# HInata-debug-board.net
KiCad netlist of a schematic drawn in EAGLE
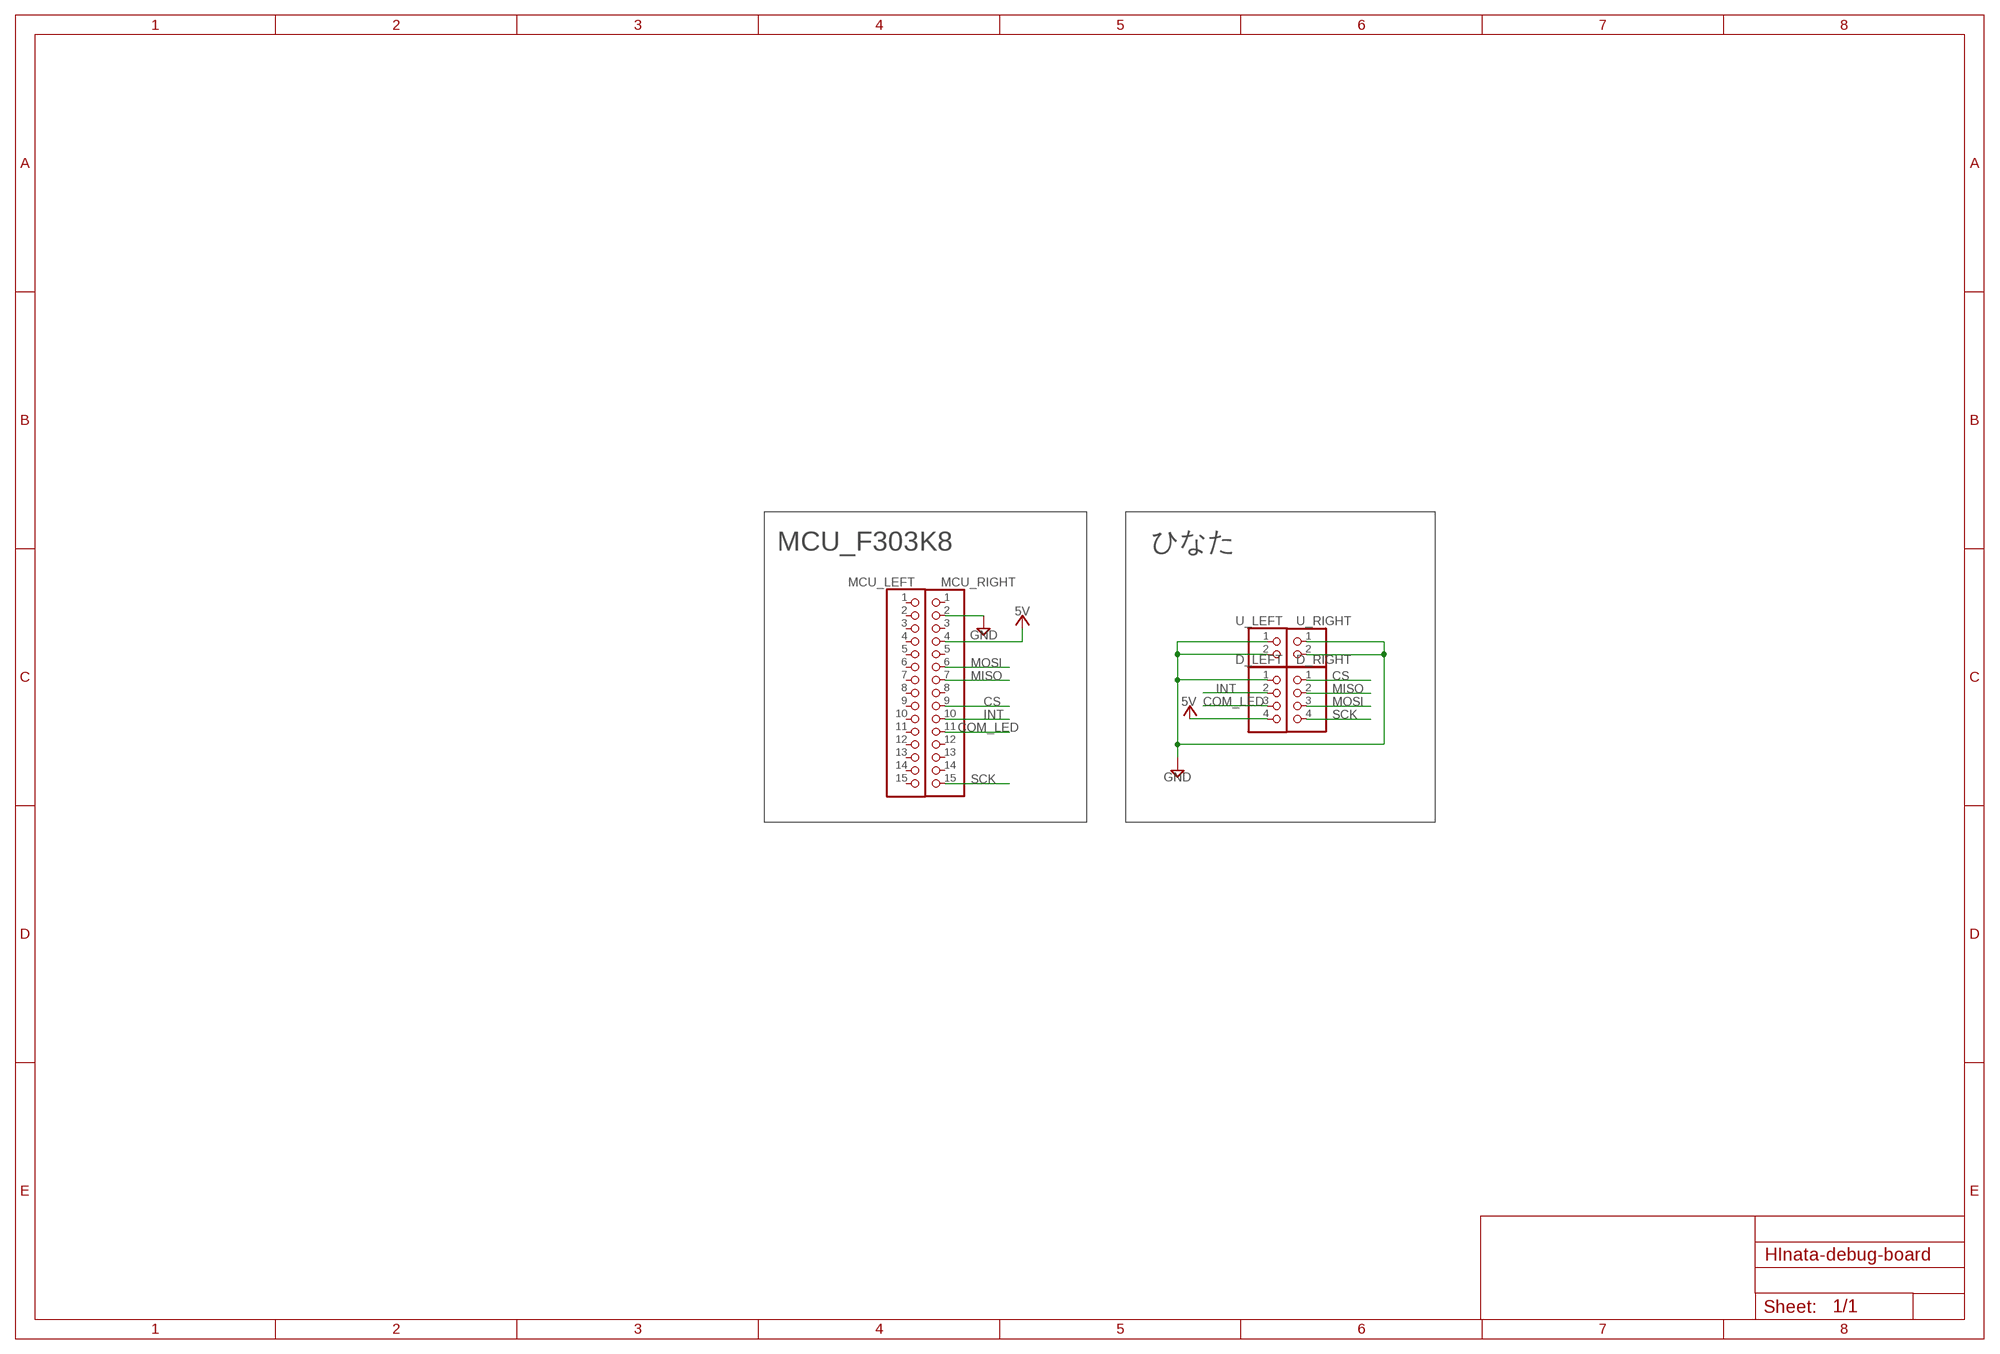
[diagram p0: schematic, sheet 1]

(export (version "E")
  (design (tool "Eeschema 10.0.6"))
  (components
    (comp (ref "D_LEFT")
      (value "PINHD-1X4")
      (footprint "eagle-import:1X04")
      (libsource (lib "eagle-import") (part "PINHD-1X4"))
    )
    (comp (ref "D_RIGHT")
      (value "PINHD-1X4")
      (footprint "eagle-import:1X04")
      (libsource (lib "eagle-import") (part "PINHD-1X4"))
    )
    (comp (ref "MCU_LEFT")
      (value "PINHD-1X15")
      (footprint "eagle-import:1X15")
      (libsource (lib "eagle-import") (part "PINHD-1X15"))
    )
    (comp (ref "MCU_RIGHT")
      (value "PINHD-1X15")
      (footprint "eagle-import:1X15")
      (libsource (lib "eagle-import") (part "PINHD-1X15"))
    )
    (comp (ref "U_LEFT")
      (value "PINHD-1X2")
      (footprint "eagle-import:1X02")
      (libsource (lib "eagle-import") (part "PINHD-1X2"))
    )
    (comp (ref "U_RIGHT")
      (value "PINHD-1X2")
      (footprint "eagle-import:1X02")
      (libsource (lib "eagle-import") (part "PINHD-1X2"))
    )
  )
  (nets
    (net (code "1") (name "/COM_LED") (class "Default")
      (node (ref "D_LEFT") (pin "3") (pinfunction "3_3") (pintype "passive"))
      (node (ref "MCU_RIGHT") (pin "11") (pinfunction "11_11") (pintype "passive"))
    )
    (net (code "2") (name "/CS") (class "Default")
      (node (ref "D_RIGHT") (pin "1") (pinfunction "1_1") (pintype "passive"))
      (node (ref "MCU_RIGHT") (pin "9") (pinfunction "9_9") (pintype "passive"))
    )
    (net (code "3") (name "/INT") (class "Default")
      (node (ref "D_LEFT") (pin "2") (pinfunction "2_2") (pintype "passive"))
      (node (ref "MCU_RIGHT") (pin "10") (pinfunction "10_10") (pintype "passive"))
    )
    (net (code "4") (name "/MISO") (class "Default")
      (node (ref "D_RIGHT") (pin "2") (pinfunction "2_2") (pintype "passive"))
      (node (ref "MCU_RIGHT") (pin "7") (pinfunction "7_7") (pintype "passive"))
    )
    (net (code "5") (name "/MOSI") (class "Default")
      (node (ref "D_RIGHT") (pin "3") (pinfunction "3_3") (pintype "passive"))
      (node (ref "MCU_RIGHT") (pin "6") (pinfunction "6_6") (pintype "passive"))
    )
    (net (code "6") (name "/SCK") (class "Default")
      (node (ref "D_RIGHT") (pin "4") (pinfunction "4_4") (pintype "passive"))
      (node (ref "MCU_RIGHT") (pin "15") (pinfunction "15_15") (pintype "passive"))
    )
    (net (code "7") (name "GND") (class "Default")
      (node (ref "D_LEFT") (pin "1") (pinfunction "1_1") (pintype "passive"))
      (node (ref "MCU_RIGHT") (pin "2") (pinfunction "2_2") (pintype "passive"))
      (node (ref "U_LEFT") (pin "1") (pinfunction "1_1") (pintype "passive"))
      (node (ref "U_LEFT") (pin "2") (pinfunction "2_2") (pintype "passive"))
      (node (ref "U_RIGHT") (pin "1") (pinfunction "1_1") (pintype "passive"))
      (node (ref "U_RIGHT") (pin "2") (pinfunction "2_2") (pintype "passive"))
    )
    (net (code "8") (name "VCC") (class "Default")
      (node (ref "D_LEFT") (pin "4") (pinfunction "4_4") (pintype "passive"))
      (node (ref "MCU_RIGHT") (pin "4") (pinfunction "4_4") (pintype "passive"))
    )
    (net (code "9") (name "unconnected-(MCU_LEFT-Pad1)") (class "Default")
      (node (ref "MCU_LEFT") (pin "1") (pinfunction "1_1") (pintype "passive"))
    )
    (net (code "10") (name "unconnected-(MCU_LEFT-Pad2)") (class "Default")
      (node (ref "MCU_LEFT") (pin "2") (pinfunction "2_2") (pintype "passive"))
    )
    (net (code "11") (name "unconnected-(MCU_LEFT-Pad3)") (class "Default")
      (node (ref "MCU_LEFT") (pin "3") (pinfunction "3_3") (pintype "passive"))
    )
    (net (code "12") (name "unconnected-(MCU_LEFT-Pad4)") (class "Default")
      (node (ref "MCU_LEFT") (pin "4") (pinfunction "4_4") (pintype "passive"))
    )
    (net (code "13") (name "unconnected-(MCU_LEFT-Pad5)") (class "Default")
      (node (ref "MCU_LEFT") (pin "5") (pinfunction "5_5") (pintype "passive"))
    )
    (net (code "14") (name "unconnected-(MCU_LEFT-Pad6)") (class "Default")
      (node (ref "MCU_LEFT") (pin "6") (pinfunction "6_6") (pintype "passive"))
    )
    (net (code "15") (name "unconnected-(MCU_LEFT-Pad7)") (class "Default")
      (node (ref "MCU_LEFT") (pin "7") (pinfunction "7_7") (pintype "passive"))
    )
    (net (code "16") (name "unconnected-(MCU_LEFT-Pad8)") (class "Default")
      (node (ref "MCU_LEFT") (pin "8") (pinfunction "8_8") (pintype "passive"))
    )
    (net (code "17") (name "unconnected-(MCU_LEFT-Pad9)") (class "Default")
      (node (ref "MCU_LEFT") (pin "9") (pinfunction "9_9") (pintype "passive"))
    )
    (net (code "18") (name "unconnected-(MCU_LEFT-Pad10)") (class "Default")
      (node (ref "MCU_LEFT") (pin "10") (pinfunction "10_10") (pintype "passive"))
    )
    (net (code "19") (name "unconnected-(MCU_LEFT-Pad11)") (class "Default")
      (node (ref "MCU_LEFT") (pin "11") (pinfunction "11_11") (pintype "passive"))
    )
    (net (code "20") (name "unconnected-(MCU_LEFT-Pad12)") (class "Default")
      (node (ref "MCU_LEFT") (pin "12") (pinfunction "12_12") (pintype "passive"))
    )
    (net (code "21") (name "unconnected-(MCU_LEFT-Pad13)") (class "Default")
      (node (ref "MCU_LEFT") (pin "13") (pinfunction "13_13") (pintype "passive"))
    )
    (net (code "22") (name "unconnected-(MCU_LEFT-Pad14)") (class "Default")
      (node (ref "MCU_LEFT") (pin "14") (pinfunction "14_14") (pintype "passive"))
    )
    (net (code "23") (name "unconnected-(MCU_LEFT-Pad15)") (class "Default")
      (node (ref "MCU_LEFT") (pin "15") (pinfunction "15_15") (pintype "passive"))
    )
    (net (code "24") (name "unconnected-(MCU_RIGHT-Pad1)") (class "Default")
      (node (ref "MCU_RIGHT") (pin "1") (pinfunction "1_1") (pintype "passive"))
    )
    (net (code "25") (name "unconnected-(MCU_RIGHT-Pad3)") (class "Default")
      (node (ref "MCU_RIGHT") (pin "3") (pinfunction "3_3") (pintype "passive"))
    )
    (net (code "26") (name "unconnected-(MCU_RIGHT-Pad5)") (class "Default")
      (node (ref "MCU_RIGHT") (pin "5") (pinfunction "5_5") (pintype "passive"))
    )
    (net (code "27") (name "unconnected-(MCU_RIGHT-Pad8)") (class "Default")
      (node (ref "MCU_RIGHT") (pin "8") (pinfunction "8_8") (pintype "passive"))
    )
    (net (code "28") (name "unconnected-(MCU_RIGHT-Pad12)") (class "Default")
      (node (ref "MCU_RIGHT") (pin "12") (pinfunction "12_12") (pintype "passive"))
    )
    (net (code "29") (name "unconnected-(MCU_RIGHT-Pad13)") (class "Default")
      (node (ref "MCU_RIGHT") (pin "13") (pinfunction "13_13") (pintype "passive"))
    )
    (net (code "30") (name "unconnected-(MCU_RIGHT-Pad14)") (class "Default")
      (node (ref "MCU_RIGHT") (pin "14") (pinfunction "14_14") (pintype "passive"))
    )
  )
)
